# untitled.net
KiCad netlist of a schematic drawn in EAGLE
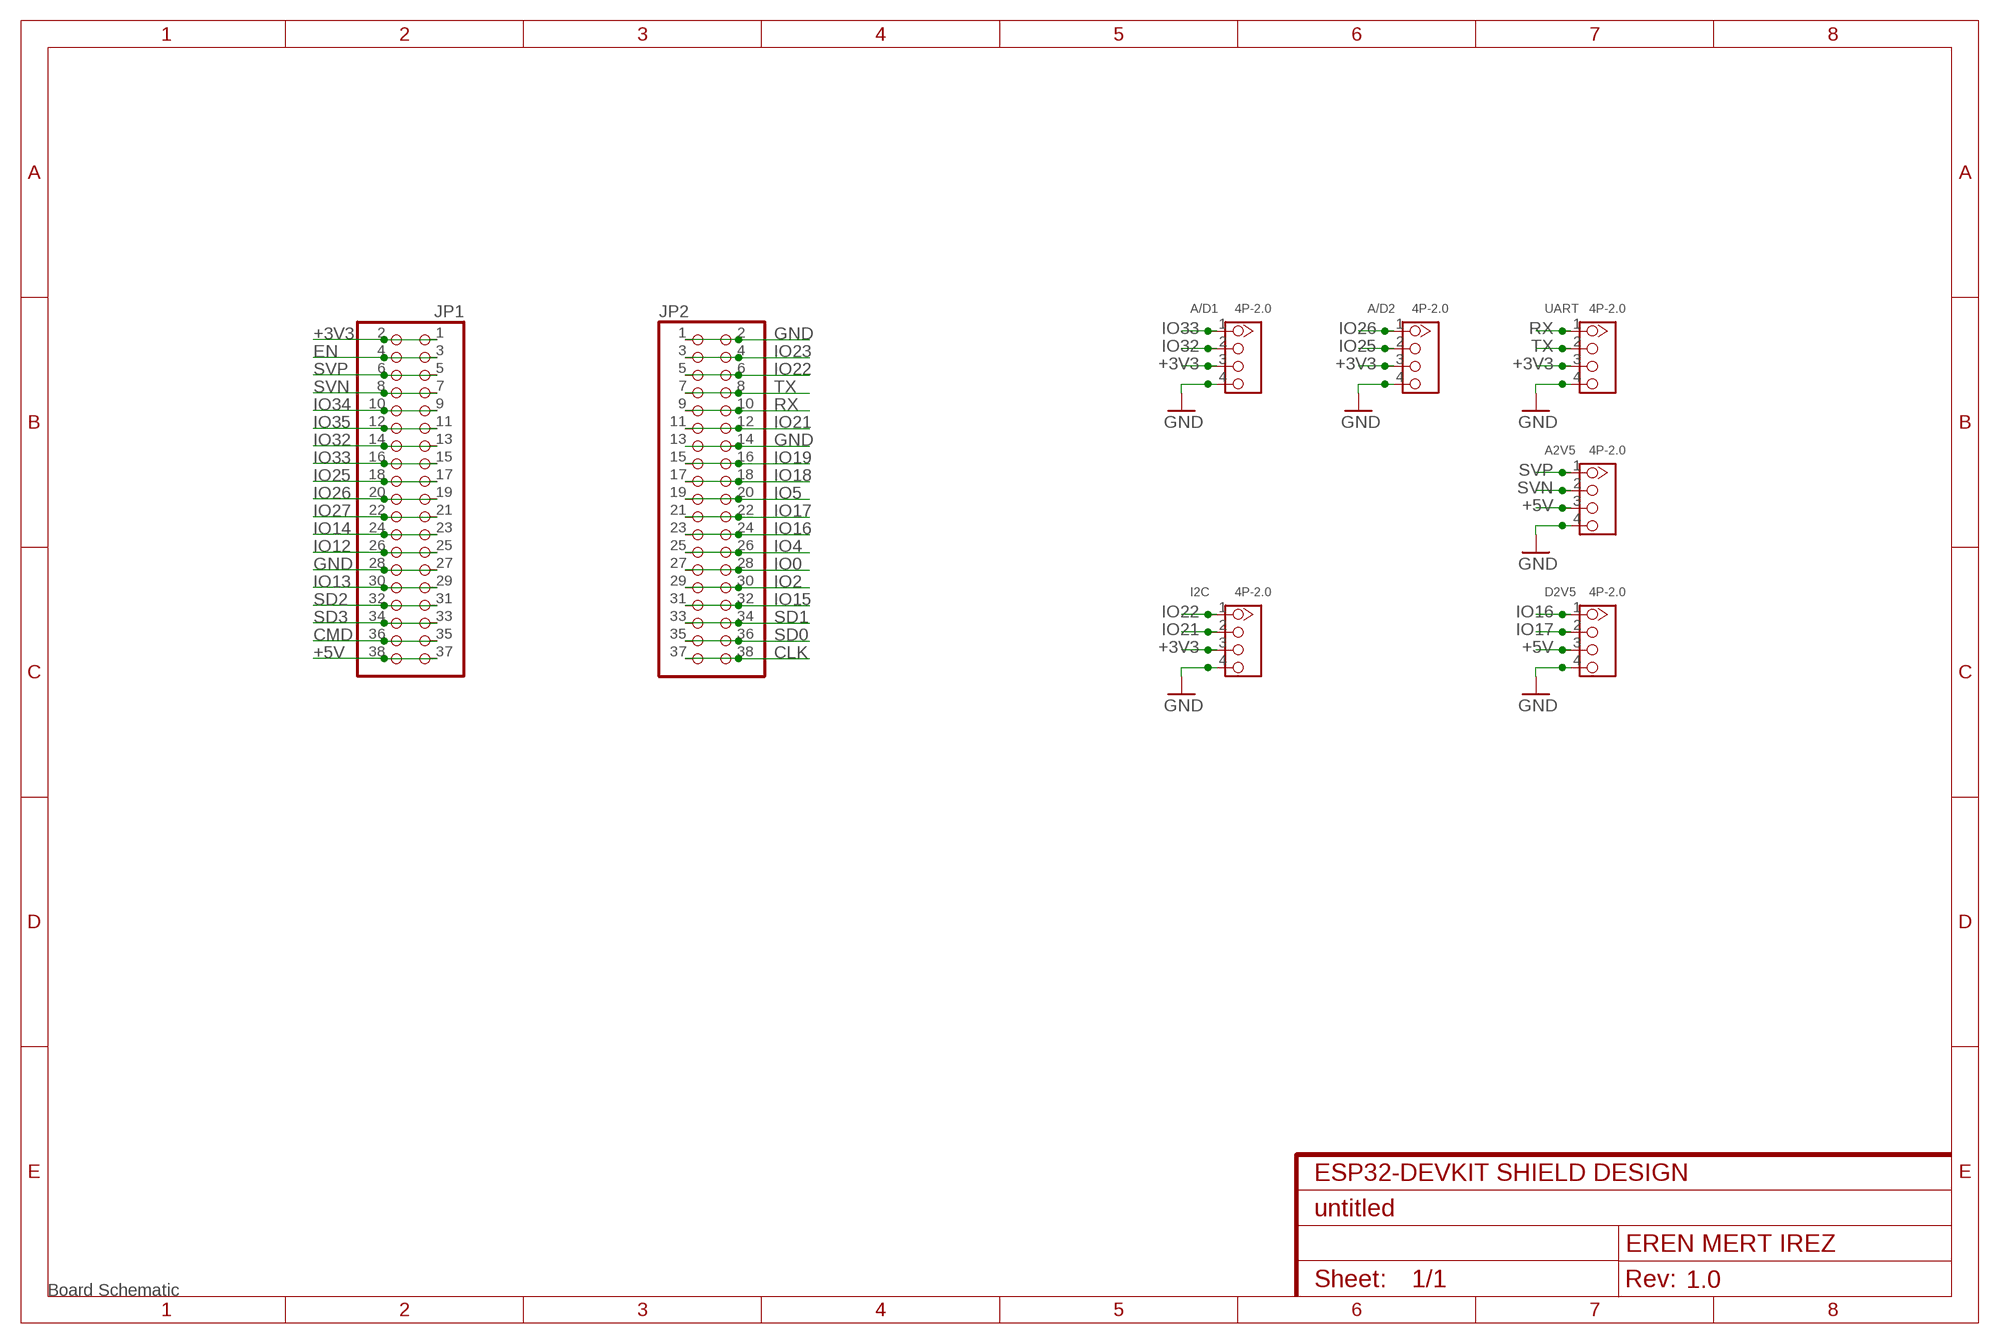
[diagram p0: schematic, sheet 1]

(export (version "E")
  (design (tool "Eeschema 10.0.6"))
  (components
    (comp (ref "A/D1")
      (value "4P-2.0")
      (footprint "eagle-import:HW4-2.0")
      (libsource (lib "eagle-import") (part "GROVE-CONNECTOR-DIP(4P-2.0)"))
    )
    (comp (ref "A/D2")
      (value "4P-2.0")
      (footprint "eagle-import:HW4-2.0")
      (libsource (lib "eagle-import") (part "GROVE-CONNECTOR-DIP(4P-2.0)"))
    )
    (comp (ref "A2V5")
      (value "4P-2.0")
      (footprint "eagle-import:HW4-2.0")
      (libsource (lib "eagle-import") (part "GROVE-CONNECTOR-DIP(4P-2.0)"))
    )
    (comp (ref "D2V5")
      (value "4P-2.0")
      (footprint "eagle-import:HW4-2.0")
      (libsource (lib "eagle-import") (part "GROVE-CONNECTOR-DIP(4P-2.0)"))
    )
    (comp (ref "I2C")
      (value "4P-2.0")
      (footprint "eagle-import:HW4-2.0")
      (libsource (lib "eagle-import") (part "GROVE-CONNECTOR-DIP(4P-2.0)"))
    )
    (comp (ref "JP1")
      (value "PINHD-2X19")
      (footprint "eagle-import:2X19")
      (libsource (lib "eagle-import") (part "PINHD-2X19"))
    )
    (comp (ref "JP2")
      (value "PINHD-2X19")
      (footprint "eagle-import:2X19")
      (libsource (lib "eagle-import") (part "PINHD-2X19"))
    )
    (comp (ref "UART")
      (value "4P-2.0")
      (footprint "eagle-import:HW4-2.0")
      (libsource (lib "eagle-import") (part "GROVE-CONNECTOR-DIP(4P-2.0)"))
    )
  )
  (nets
    (net (code "1") (name "/+3V3") (class "Default")
      (node (ref "A/D1") (pin "3") (pinfunction "3_3") (pintype "bidirectional"))
      (node (ref "A/D2") (pin "3") (pinfunction "3_3") (pintype "bidirectional"))
      (node (ref "I2C") (pin "3") (pinfunction "3_3") (pintype "bidirectional"))
      (node (ref "JP1") (pin "1") (pinfunction "1_1") (pintype "passive"))
      (node (ref "JP1") (pin "2") (pinfunction "2_2") (pintype "passive"))
      (node (ref "UART") (pin "3") (pinfunction "3_3") (pintype "bidirectional"))
    )
    (net (code "2") (name "/+5V") (class "Default")
      (node (ref "A2V5") (pin "3") (pinfunction "3_3") (pintype "bidirectional"))
      (node (ref "D2V5") (pin "3") (pinfunction "3_3") (pintype "bidirectional"))
      (node (ref "JP1") (pin "37") (pinfunction "37_37") (pintype "passive"))
      (node (ref "JP1") (pin "38") (pinfunction "38_38") (pintype "passive"))
    )
    (net (code "3") (name "/CLK") (class "Default")
      (node (ref "JP2") (pin "37") (pinfunction "37_37") (pintype "passive"))
      (node (ref "JP2") (pin "38") (pinfunction "38_38") (pintype "passive"))
    )
    (net (code "4") (name "/CMD") (class "Default")
      (node (ref "JP1") (pin "35") (pinfunction "35_35") (pintype "passive"))
      (node (ref "JP1") (pin "36") (pinfunction "36_36") (pintype "passive"))
    )
    (net (code "5") (name "/EN") (class "Default")
      (node (ref "JP1") (pin "3") (pinfunction "3_3") (pintype "passive"))
      (node (ref "JP1") (pin "4") (pinfunction "4_4") (pintype "passive"))
    )
    (net (code "6") (name "/IO0") (class "Default")
      (node (ref "JP2") (pin "27") (pinfunction "27_27") (pintype "passive"))
      (node (ref "JP2") (pin "28") (pinfunction "28_28") (pintype "passive"))
    )
    (net (code "7") (name "/IO2") (class "Default")
      (node (ref "JP2") (pin "29") (pinfunction "29_29") (pintype "passive"))
      (node (ref "JP2") (pin "30") (pinfunction "30_30") (pintype "passive"))
    )
    (net (code "8") (name "/IO4") (class "Default")
      (node (ref "JP2") (pin "25") (pinfunction "25_25") (pintype "passive"))
      (node (ref "JP2") (pin "26") (pinfunction "26_26") (pintype "passive"))
    )
    (net (code "9") (name "/IO5") (class "Default")
      (node (ref "JP2") (pin "19") (pinfunction "19_19") (pintype "passive"))
      (node (ref "JP2") (pin "20") (pinfunction "20_20") (pintype "passive"))
    )
    (net (code "10") (name "/IO12") (class "Default")
      (node (ref "JP1") (pin "25") (pinfunction "25_25") (pintype "passive"))
      (node (ref "JP1") (pin "26") (pinfunction "26_26") (pintype "passive"))
    )
    (net (code "11") (name "/IO13") (class "Default")
      (node (ref "JP1") (pin "29") (pinfunction "29_29") (pintype "passive"))
      (node (ref "JP1") (pin "30") (pinfunction "30_30") (pintype "passive"))
    )
    (net (code "12") (name "/IO14") (class "Default")
      (node (ref "JP1") (pin "23") (pinfunction "23_23") (pintype "passive"))
      (node (ref "JP1") (pin "24") (pinfunction "24_24") (pintype "passive"))
    )
    (net (code "13") (name "/IO15") (class "Default")
      (node (ref "JP2") (pin "31") (pinfunction "31_31") (pintype "passive"))
      (node (ref "JP2") (pin "32") (pinfunction "32_32") (pintype "passive"))
    )
    (net (code "14") (name "/IO16") (class "Default")
      (node (ref "D2V5") (pin "1") (pinfunction "1_1") (pintype "bidirectional"))
      (node (ref "JP2") (pin "23") (pinfunction "23_23") (pintype "passive"))
      (node (ref "JP2") (pin "24") (pinfunction "24_24") (pintype "passive"))
    )
    (net (code "15") (name "/IO17") (class "Default")
      (node (ref "D2V5") (pin "2") (pinfunction "2_2") (pintype "bidirectional"))
      (node (ref "JP2") (pin "21") (pinfunction "21_21") (pintype "passive"))
      (node (ref "JP2") (pin "22") (pinfunction "22_22") (pintype "passive"))
    )
    (net (code "16") (name "/IO18") (class "Default")
      (node (ref "JP2") (pin "17") (pinfunction "17_17") (pintype "passive"))
      (node (ref "JP2") (pin "18") (pinfunction "18_18") (pintype "passive"))
    )
    (net (code "17") (name "/IO19") (class "Default")
      (node (ref "JP2") (pin "15") (pinfunction "15_15") (pintype "passive"))
      (node (ref "JP2") (pin "16") (pinfunction "16_16") (pintype "passive"))
    )
    (net (code "18") (name "/IO21") (class "Default")
      (node (ref "I2C") (pin "2") (pinfunction "2_2") (pintype "bidirectional"))
      (node (ref "JP2") (pin "11") (pinfunction "11_11") (pintype "passive"))
      (node (ref "JP2") (pin "12") (pinfunction "12_12") (pintype "passive"))
    )
    (net (code "19") (name "/IO22") (class "Default")
      (node (ref "I2C") (pin "1") (pinfunction "1_1") (pintype "bidirectional"))
      (node (ref "JP2") (pin "5") (pinfunction "5_5") (pintype "passive"))
      (node (ref "JP2") (pin "6") (pinfunction "6_6") (pintype "passive"))
    )
    (net (code "20") (name "/IO23") (class "Default")
      (node (ref "JP2") (pin "3") (pinfunction "3_3") (pintype "passive"))
      (node (ref "JP2") (pin "4") (pinfunction "4_4") (pintype "passive"))
    )
    (net (code "21") (name "/IO25") (class "Default")
      (node (ref "A/D2") (pin "2") (pinfunction "2_2") (pintype "bidirectional"))
      (node (ref "JP1") (pin "17") (pinfunction "17_17") (pintype "passive"))
      (node (ref "JP1") (pin "18") (pinfunction "18_18") (pintype "passive"))
    )
    (net (code "22") (name "/IO26") (class "Default")
      (node (ref "A/D2") (pin "1") (pinfunction "1_1") (pintype "bidirectional"))
      (node (ref "JP1") (pin "19") (pinfunction "19_19") (pintype "passive"))
      (node (ref "JP1") (pin "20") (pinfunction "20_20") (pintype "passive"))
    )
    (net (code "23") (name "/IO27") (class "Default")
      (node (ref "JP1") (pin "21") (pinfunction "21_21") (pintype "passive"))
      (node (ref "JP1") (pin "22") (pinfunction "22_22") (pintype "passive"))
    )
    (net (code "24") (name "/IO32") (class "Default")
      (node (ref "A/D1") (pin "2") (pinfunction "2_2") (pintype "bidirectional"))
      (node (ref "JP1") (pin "13") (pinfunction "13_13") (pintype "passive"))
      (node (ref "JP1") (pin "14") (pinfunction "14_14") (pintype "passive"))
    )
    (net (code "25") (name "/IO33") (class "Default")
      (node (ref "A/D1") (pin "1") (pinfunction "1_1") (pintype "bidirectional"))
      (node (ref "JP1") (pin "15") (pinfunction "15_15") (pintype "passive"))
      (node (ref "JP1") (pin "16") (pinfunction "16_16") (pintype "passive"))
    )
    (net (code "26") (name "/IO34") (class "Default")
      (node (ref "JP1") (pin "10") (pinfunction "10_10") (pintype "passive"))
      (node (ref "JP1") (pin "9") (pinfunction "9_9") (pintype "passive"))
    )
    (net (code "27") (name "/IO35") (class "Default")
      (node (ref "JP1") (pin "11") (pinfunction "11_11") (pintype "passive"))
      (node (ref "JP1") (pin "12") (pinfunction "12_12") (pintype "passive"))
    )
    (net (code "28") (name "/RX") (class "Default")
      (node (ref "JP2") (pin "10") (pinfunction "10_10") (pintype "passive"))
      (node (ref "JP2") (pin "9") (pinfunction "9_9") (pintype "passive"))
      (node (ref "UART") (pin "1") (pinfunction "1_1") (pintype "bidirectional"))
    )
    (net (code "29") (name "/SD0") (class "Default")
      (node (ref "JP2") (pin "35") (pinfunction "35_35") (pintype "passive"))
      (node (ref "JP2") (pin "36") (pinfunction "36_36") (pintype "passive"))
    )
    (net (code "30") (name "/SD1") (class "Default")
      (node (ref "JP2") (pin "33") (pinfunction "33_33") (pintype "passive"))
      (node (ref "JP2") (pin "34") (pinfunction "34_34") (pintype "passive"))
    )
    (net (code "31") (name "/SD2") (class "Default")
      (node (ref "JP1") (pin "31") (pinfunction "31_31") (pintype "passive"))
      (node (ref "JP1") (pin "32") (pinfunction "32_32") (pintype "passive"))
    )
    (net (code "32") (name "/SD3") (class "Default")
      (node (ref "JP1") (pin "33") (pinfunction "33_33") (pintype "passive"))
      (node (ref "JP1") (pin "34") (pinfunction "34_34") (pintype "passive"))
    )
    (net (code "33") (name "/SVN") (class "Default")
      (node (ref "A2V5") (pin "2") (pinfunction "2_2") (pintype "bidirectional"))
      (node (ref "JP1") (pin "7") (pinfunction "7_7") (pintype "passive"))
      (node (ref "JP1") (pin "8") (pinfunction "8_8") (pintype "passive"))
    )
    (net (code "34") (name "/SVP") (class "Default")
      (node (ref "A2V5") (pin "1") (pinfunction "1_1") (pintype "bidirectional"))
      (node (ref "JP1") (pin "5") (pinfunction "5_5") (pintype "passive"))
      (node (ref "JP1") (pin "6") (pinfunction "6_6") (pintype "passive"))
    )
    (net (code "35") (name "/TX") (class "Default")
      (node (ref "JP2") (pin "7") (pinfunction "7_7") (pintype "passive"))
      (node (ref "JP2") (pin "8") (pinfunction "8_8") (pintype "passive"))
      (node (ref "UART") (pin "2") (pinfunction "2_2") (pintype "bidirectional"))
    )
    (net (code "36") (name "GND") (class "Default")
      (node (ref "A/D1") (pin "4") (pinfunction "4_4") (pintype "bidirectional"))
      (node (ref "A/D2") (pin "4") (pinfunction "4_4") (pintype "bidirectional"))
      (node (ref "A2V5") (pin "4") (pinfunction "4_4") (pintype "bidirectional"))
      (node (ref "D2V5") (pin "4") (pinfunction "4_4") (pintype "bidirectional"))
      (node (ref "I2C") (pin "4") (pinfunction "4_4") (pintype "bidirectional"))
      (node (ref "JP1") (pin "27") (pinfunction "27_27") (pintype "passive"))
      (node (ref "JP1") (pin "28") (pinfunction "28_28") (pintype "passive"))
      (node (ref "JP2") (pin "1") (pinfunction "1_1") (pintype "passive"))
      (node (ref "JP2") (pin "13") (pinfunction "13_13") (pintype "passive"))
      (node (ref "JP2") (pin "14") (pinfunction "14_14") (pintype "passive"))
      (node (ref "JP2") (pin "2") (pinfunction "2_2") (pintype "passive"))
      (node (ref "UART") (pin "4") (pinfunction "4_4") (pintype "bidirectional"))
    )
  )
)
